# BlinkyBall.net
KiCad netlist of a schematic drawn in EAGLE
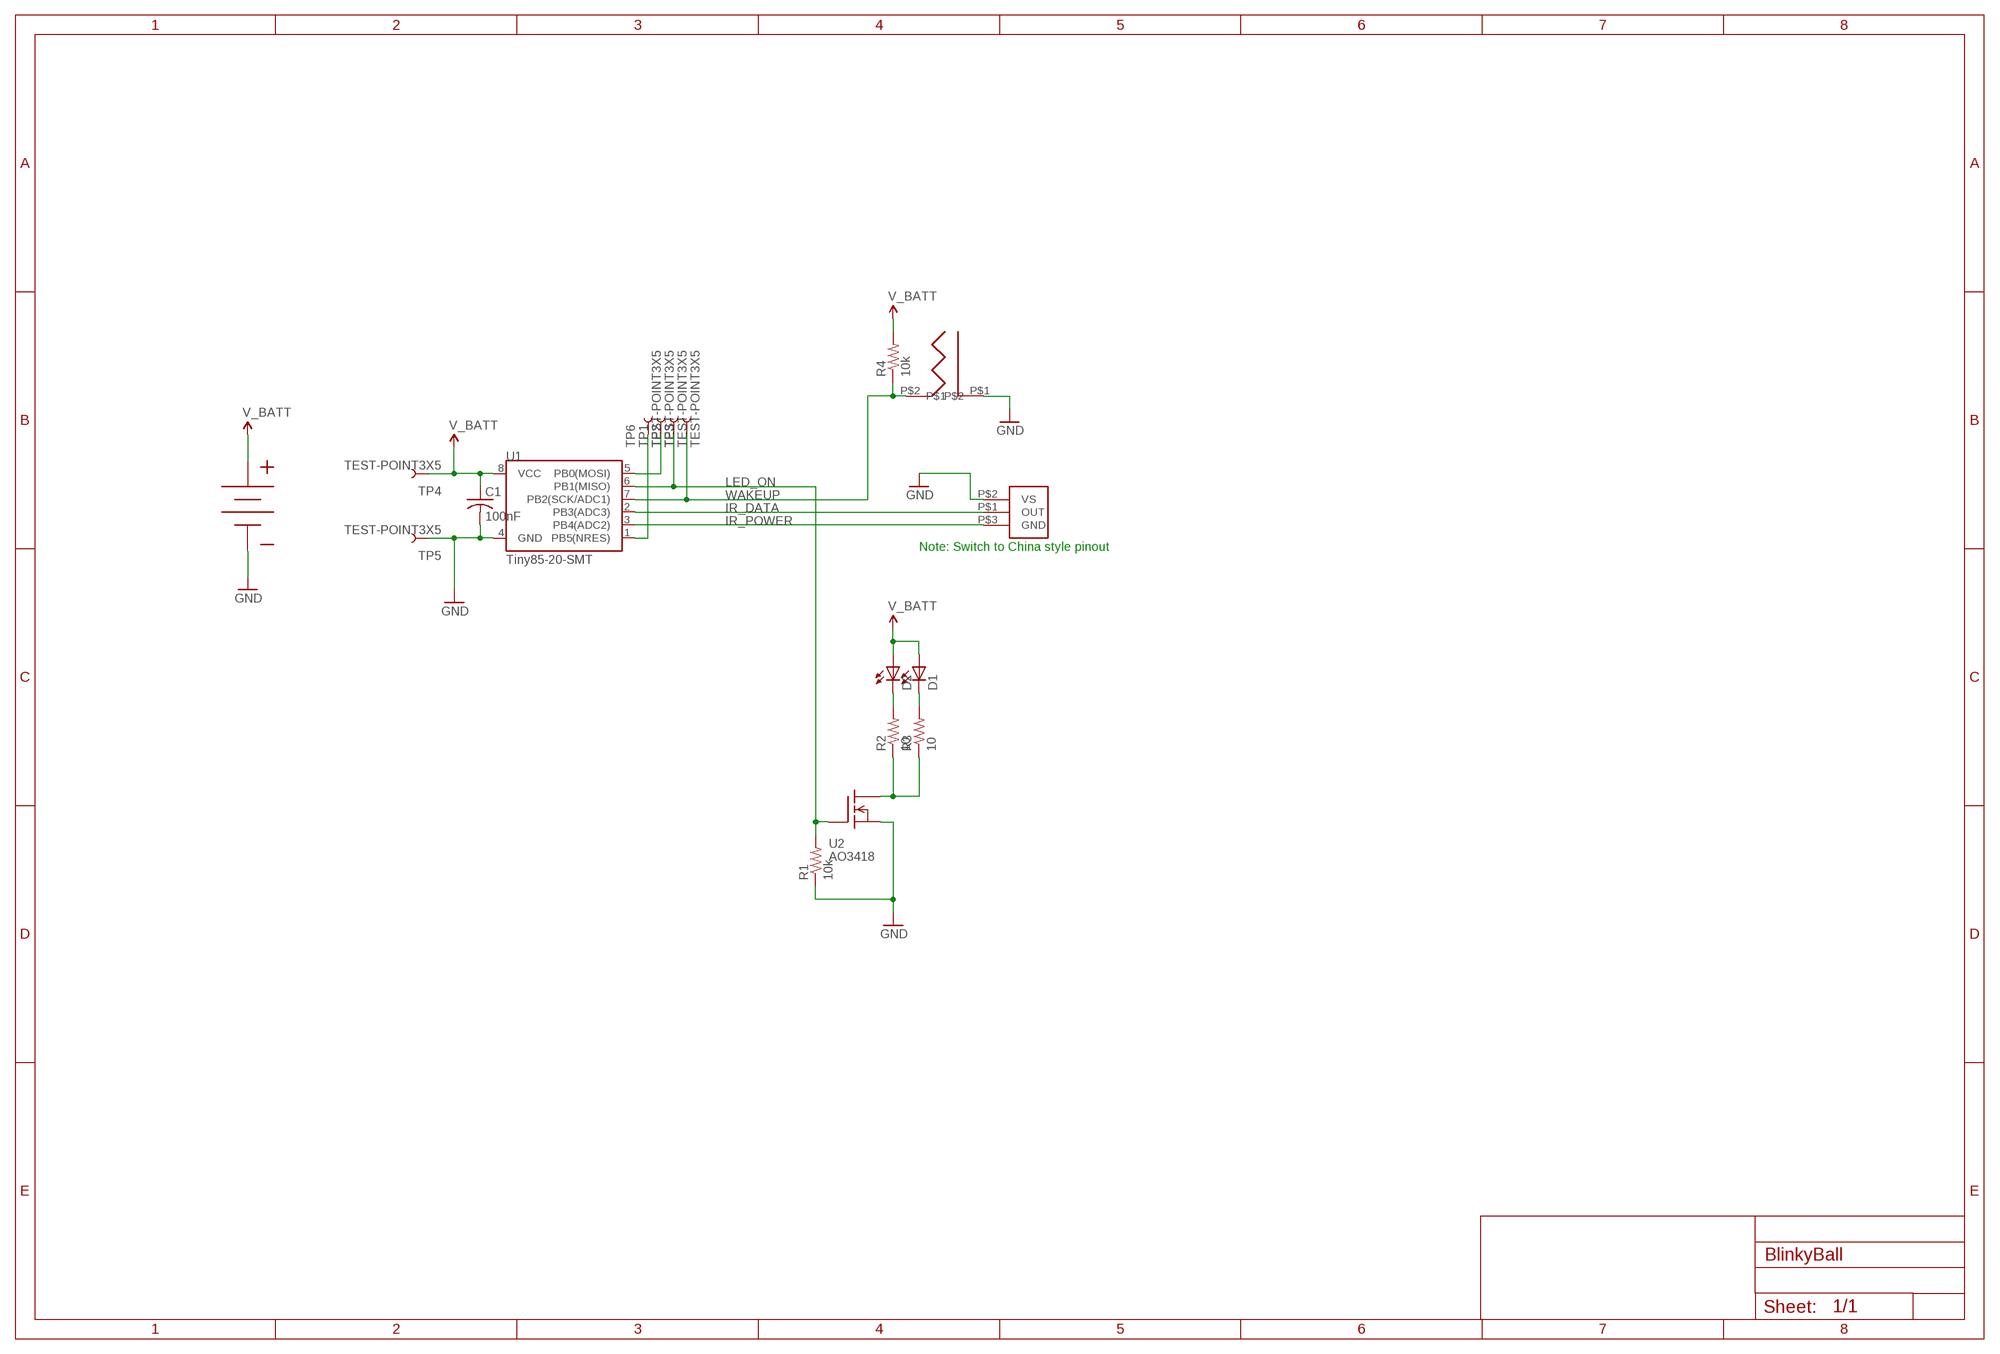
[diagram p0: schematic, sheet 1]

(export (version "E")
  (design (tool "Eeschema 10.0.6"))
  (components
    (comp (ref "C1")
      (value "100nF")
      (footprint "eagle-import:C0603")
      (libsource (lib "eagle-import") (part "C-USC0603"))
    )
    (comp (ref "D1")
      (value "LED5MM")
      (footprint "eagle-import:LED5MM")
      (libsource (lib "eagle-import") (part "LED5MM"))
    )
    (comp (ref "D2")
      (value "LED5MM")
      (footprint "eagle-import:LED5MM")
      (libsource (lib "eagle-import") (part "LED5MM"))
    )
    (comp (ref "J1")
      (value "SW-18015P")
      (footprint "eagle-import:SW-18015P")
      (libsource (lib "eagle-import") (part "SW-18015P"))
    )
    (comp (ref "J2")
      (value "BATTERY_BUTTON_CELLAG3")
      (footprint "eagle-import:BATTERY_COVER_AG3")
      (libsource (lib "eagle-import") (part "BATTERY_BUTTON_CELLAG3"))
    )
    (comp (ref "R1")
      (value "10k")
      (footprint "eagle-import:R0603")
      (libsource (lib "eagle-import") (part "R-US_R0603"))
    )
    (comp (ref "R2")
      (value "10")
      (footprint "eagle-import:R0603")
      (libsource (lib "eagle-import") (part "R-US_R0603"))
    )
    (comp (ref "R3")
      (value "10")
      (footprint "eagle-import:R0603")
      (libsource (lib "eagle-import") (part "R-US_R0603"))
    )
    (comp (ref "R4")
      (value "10k")
      (footprint "eagle-import:R0603")
      (libsource (lib "eagle-import") (part "R-US_R0603"))
    )
    (comp (ref "TP1")
      (value "TEST-POINT3X5")
      (footprint "eagle-import:PAD.03X.05")
      (libsource (lib "eagle-import") (part "TEST-POINT3X5"))
    )
    (comp (ref "TP2")
      (value "TEST-POINT3X5")
      (footprint "eagle-import:PAD.03X.05")
      (libsource (lib "eagle-import") (part "TEST-POINT3X5"))
    )
    (comp (ref "TP3")
      (value "TEST-POINT3X5")
      (footprint "eagle-import:PAD.03X.05")
      (libsource (lib "eagle-import") (part "TEST-POINT3X5"))
    )
    (comp (ref "TP4")
      (value "TEST-POINT3X5")
      (footprint "eagle-import:PAD.03X.05")
      (libsource (lib "eagle-import") (part "TEST-POINT3X5"))
    )
    (comp (ref "TP5")
      (value "TEST-POINT3X5")
      (footprint "eagle-import:PAD.03X.05")
      (libsource (lib "eagle-import") (part "TEST-POINT3X5"))
    )
    (comp (ref "TP6")
      (value "TEST-POINT3X5")
      (footprint "eagle-import:PAD.03X.05")
      (libsource (lib "eagle-import") (part "TEST-POINT3X5"))
    )
    (comp (ref "U1")
      (value "Tiny85-20-SMT")
      (footprint "eagle-import:SO08-EIAJ")
      (libsource (lib "eagle-import") (part "ATTINY45TINY85-20-SMT"))
    )
    (comp (ref "U2")
      (value "AO3418")
      (footprint "eagle-import:SOT23")
      (libsource (lib "eagle-import") (part "N_MOSFETSOT23"))
    )
    (comp (ref "U3")
      (value "TSOP321")
      (footprint "eagle-import:TSOP321")
      (libsource (lib "eagle-import") (part "TSOP321"))
    )
  )
  (nets
    (net (code "1") (name "/IR_DATA") (class "Default")
      (node (ref "U1") (pin "2") (pinfunction "PB3(ADC3)_2") (pintype "bidirectional"))
      (node (ref "U3") (pin "P$1") (pinfunction "OUT_P$1") (pintype "bidirectional"))
    )
    (net (code "2") (name "/IR_POWER") (class "Default")
      (node (ref "U1") (pin "3") (pinfunction "PB4(ADC2)_3") (pintype "bidirectional"))
      (node (ref "U3") (pin "P$3") (pinfunction "GND_P$3") (pintype "bidirectional"))
    )
    (net (code "3") (name "/LED_ON") (class "Default")
      (node (ref "R1") (pin "2") (pinfunction "2_2") (pintype "passive"))
      (node (ref "TP2") (pin "P$1") (pinfunction "1_P$1") (pintype "bidirectional"))
      (node (ref "U1") (pin "6") (pinfunction "PB1(MISO)_6") (pintype "bidirectional"))
      (node (ref "U2") (pin "1") (pinfunction "G_1") (pintype "bidirectional"))
    )
    (net (code "4") (name "/WAKEUP") (class "Default")
      (node (ref "J1") (pin "P$2") (pinfunction "P$2_P$2") (pintype "bidirectional"))
      (node (ref "R4") (pin "1") (pinfunction "1_1") (pintype "passive"))
      (node (ref "TP3") (pin "P$1") (pinfunction "1_P$1") (pintype "bidirectional"))
      (node (ref "U1") (pin "7") (pinfunction "PB2(SCK/ADC1)_7") (pintype "bidirectional"))
    )
    (net (code "5") (name "GND") (class "Default")
      (node (ref "C1") (pin "2") (pinfunction "2_2") (pintype "passive"))
      (node (ref "J1") (pin "P$1") (pinfunction "P$1_P$1") (pintype "bidirectional"))
      (node (ref "J2") (pin "-") (pinfunction "-_-") (pintype "power_in"))
      (node (ref "R1") (pin "1") (pinfunction "1_1") (pintype "passive"))
      (node (ref "TP5") (pin "P$1") (pinfunction "1_P$1") (pintype "bidirectional"))
      (node (ref "U1") (pin "4") (pinfunction "GND_4") (pintype "bidirectional"))
      (node (ref "U2") (pin "2") (pinfunction "S_2") (pintype "bidirectional"))
      (node (ref "U3") (pin "P$2") (pinfunction "VS_P$2") (pintype "bidirectional"))
    )
    (net (code "6") (name "Net-(D1-C)") (class "Default")
      (node (ref "D1") (pin "K") (pinfunction "C_K") (pintype "passive"))
      (node (ref "R3") (pin "2") (pinfunction "2_2") (pintype "passive"))
    )
    (net (code "7") (name "Net-(D2-C)") (class "Default")
      (node (ref "D2") (pin "K") (pinfunction "C_K") (pintype "passive"))
      (node (ref "R2") (pin "2") (pinfunction "2_2") (pintype "passive"))
    )
    (net (code "8") (name "Net-(TP1-1)") (class "Default")
      (node (ref "TP1") (pin "P$1") (pinfunction "1_P$1") (pintype "bidirectional"))
      (node (ref "U1") (pin "5") (pinfunction "PB0(MOSI)_5") (pintype "bidirectional"))
    )
    (net (code "9") (name "Net-(TP6-1)") (class "Default")
      (node (ref "TP6") (pin "P$1") (pinfunction "1_P$1") (pintype "bidirectional"))
      (node (ref "U1") (pin "1") (pinfunction "PB5(NRES)_1") (pintype "bidirectional"))
    )
    (net (code "10") (name "Net-(U2-D)") (class "Default")
      (node (ref "R2") (pin "1") (pinfunction "1_1") (pintype "passive"))
      (node (ref "R3") (pin "1") (pinfunction "1_1") (pintype "passive"))
      (node (ref "U2") (pin "3") (pinfunction "D_3") (pintype "bidirectional"))
    )
    (net (code "11") (name "V_BATT") (class "Default")
      (node (ref "C1") (pin "1") (pinfunction "1_1") (pintype "passive"))
      (node (ref "D1") (pin "A") (pinfunction "A_A") (pintype "passive"))
      (node (ref "D2") (pin "A") (pinfunction "A_A") (pintype "passive"))
      (node (ref "J2") (pin "+1") (pinfunction "+_+1") (pintype "power_in"))
      (node (ref "J2") (pin "+2") (pinfunction "+_+2") (pintype "power_in"))
      (node (ref "J2") (pin "+3") (pinfunction "+_+3") (pintype "power_in"))
      (node (ref "J2") (pin "+4") (pinfunction "+_+4") (pintype "power_in"))
      (node (ref "R4") (pin "2") (pinfunction "2_2") (pintype "passive"))
      (node (ref "TP4") (pin "P$1") (pinfunction "1_P$1") (pintype "bidirectional"))
      (node (ref "U1") (pin "8") (pinfunction "VCC_8") (pintype "bidirectional"))
    )
  )
)
